# Pulsed_IR_LED.net
KiCad netlist of a schematic drawn in Altium Designer
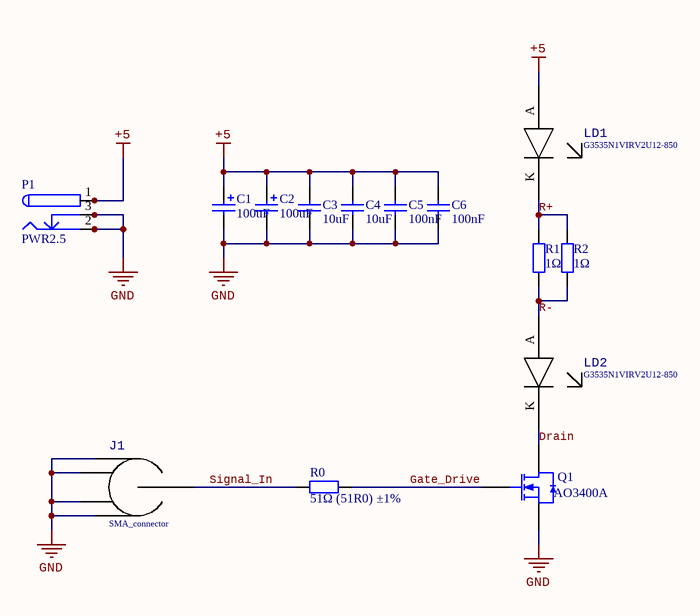
[diagram p0: Pulsed_IR_LED.SchDoc]

(export (version "E")
  (design (tool "Eeschema 10.0.6"))
  (components
    (comp (ref "C1")
      (value "100uF")
      (footprint "CASE-B_3528")
      (description "钽电容")
      (libsource (lib "JLC SMT Devices") (part "3528 100uF (107) 10% 6.3V"))
    )
    (comp (ref "C2")
      (value "100uF")
      (footprint "CASE-B_3528")
      (description "钽电容")
      (libsource (lib "JLC SMT Devices") (part "3528 100uF (107) 10% 6.3V"))
    )
    (comp (ref "C3")
      (value "10uF")
      (footprint "0805_C")
      (description "贴片电容")
      (libsource (lib "JLC SMT Devices") (part "0805 10uF (106) 10% 25V"))
    )
    (comp (ref "C4")
      (value "10uF")
      (footprint "0805_C")
      (description "贴片电容")
      (libsource (lib "JLC SMT Devices") (part "0805 10uF (106) 10% 25V"))
    )
    (comp (ref "C5")
      (value "100nF")
      (footprint "0603_C")
      (description "贴片电容")
      (libsource (lib "JLC SMT Devices") (part "0603 100nF (104) 10% 50V"))
    )
    (comp (ref "C6")
      (value "100nF")
      (footprint "0603_C")
      (description "贴片电容")
      (libsource (lib "JLC SMT Devices") (part "0603 100nF (104) 10% 50V"))
    )
    (comp (ref "J1")
      (value "SMA_connector")
      (footprint "SMA_header")
      (libsource (lib "SMA connector") (part "SMA_connector"))
    )
    (comp (ref "LD1")
      (value "G3535N1VIRV2U12-850")
      (footprint "3535VIR")
      (libsource (lib "IR_Vcsels") (part "G3535N1VIRV2U12-850"))
    )
    (comp (ref "LD2")
      (value "G3535N1VIRV2U12-850")
      (footprint "3535VIR")
      (libsource (lib "IR_Vcsels") (part "G3535N1VIRV2U12-850"))
    )
    (comp (ref "P1")
      (value "PWR2.5")
      (footprint "KLD-0202")
      (description "Low Voltage Power Supply Connector")
      (fields (field (name "PUBLISHER") "Altium Limited"))
      (libsource (lib "Miscellaneous Connectors") (part "PWR2.5"))
    )
    (comp (ref "Q1")
      (value "AO3400A")
      (footprint "SOT-23-3L")
      (description "MOS(场效应管)")
      (libsource (lib "JLC SMT Devices") (part "AO3400A N道沟 X0YV1T SOT-23"))
    )
    (comp (ref "R0")
      (value "51Ω (51R0) ±1%")
      (footprint "0402_R")
      (description "贴片电阻")
      (libsource (lib "JLC SMT Devices") (part "0402 51Ω (51R0) 1%"))
    )
    (comp (ref "R1")
      (value "1Ω")
      (footprint "1206_R")
      (description "贴片电阻")
      (libsource (lib "JLC SMT Devices") (part "1206 1Ω (1R00) 1%"))
    )
    (comp (ref "R2")
      (value "1Ω")
      (footprint "1206_R")
      (description "贴片电阻")
      (libsource (lib "JLC SMT Devices") (part "1206 1Ω (1R00) 1%"))
    )
  )
  (nets
    (net (code "1") (name "+5") (class "Default")
      (node (ref "C1") (pin "1") (pinfunction "1_1") (pintype "passive"))
      (node (ref "C2") (pin "1") (pinfunction "1_1") (pintype "passive"))
      (node (ref "C3") (pin "1") (pinfunction "1_1") (pintype "passive"))
      (node (ref "C4") (pin "1") (pinfunction "1_1") (pintype "passive"))
      (node (ref "C5") (pin "1") (pinfunction "1_1") (pintype "passive"))
      (node (ref "C6") (pin "1") (pinfunction "1_1") (pintype "passive"))
      (node (ref "LD1") (pin "A") (pinfunction "Anode_A") (pintype "passive"))
      (node (ref "P1") (pin "1") (pinfunction "1_1") (pintype "power_in"))
      (node (ref "P1") (pin "1A") (pinfunction "1A_1A") (pintype "power_in"))
      (node (ref "P1") (pin "1B") (pinfunction "1B_1B") (pintype "power_in"))
    )
    (net (code "2") (name "/Drain") (class "Default")
      (node (ref "LD2") (pin "K") (pinfunction "Cathode_K") (pintype "passive"))
      (node (ref "Q1") (pin "3") (pinfunction "D_3") (pintype "passive"))
    )
    (net (code "3") (name "/Gate_Drive") (class "Default")
      (node (ref "Q1") (pin "1") (pinfunction "G_1") (pintype "passive"))
      (node (ref "R0") (pin "2") (pinfunction "2_2") (pintype "passive"))
    )
    (net (code "4") (name "/R+") (class "Default")
      (node (ref "LD1") (pin "K") (pinfunction "Cathode_K") (pintype "passive"))
      (node (ref "R1") (pin "1") (pinfunction "1_1") (pintype "passive"))
      (node (ref "R2") (pin "1") (pinfunction "1_1") (pintype "passive"))
    )
    (net (code "5") (name "/R-") (class "Default")
      (node (ref "LD2") (pin "A") (pinfunction "Anode_A") (pintype "passive"))
      (node (ref "R1") (pin "2") (pinfunction "2_2") (pintype "passive"))
      (node (ref "R2") (pin "2") (pinfunction "2_2") (pintype "passive"))
    )
    (net (code "6") (name "/Signal_In") (class "Default")
      (node (ref "J1") (pin "1") (pinfunction "CORE_1") (pintype "passive"))
      (node (ref "R0") (pin "1") (pinfunction "1_1") (pintype "passive"))
    )
    (net (code "7") (name "GND") (class "Default")
      (node (ref "C1") (pin "2") (pinfunction "2_2") (pintype "passive"))
      (node (ref "C2") (pin "2") (pinfunction "2_2") (pintype "passive"))
      (node (ref "C3") (pin "2") (pinfunction "2_2") (pintype "passive"))
      (node (ref "C4") (pin "2") (pinfunction "2_2") (pintype "passive"))
      (node (ref "C5") (pin "2") (pinfunction "2_2") (pintype "passive"))
      (node (ref "C6") (pin "2") (pinfunction "2_2") (pintype "passive"))
      (node (ref "J1") (pin "2") (pinfunction "GND_2") (pintype "passive"))
      (node (ref "J1") (pin "3") (pinfunction "GND_3") (pintype "passive"))
      (node (ref "J1") (pin "4") (pinfunction "GND_4") (pintype "passive"))
      (node (ref "J1") (pin "5") (pinfunction "GND_5") (pintype "passive"))
      (node (ref "P1") (pin "2") (pinfunction "2_2") (pintype "power_in"))
      (node (ref "P1") (pin "2A") (pinfunction "2A_2A") (pintype "power_in"))
      (node (ref "P1") (pin "2B") (pinfunction "2B_2B") (pintype "power_in"))
      (node (ref "P1") (pin "3") (pinfunction "3_3") (pintype "power_in"))
      (node (ref "P1") (pin "3A") (pinfunction "3A_3A") (pintype "power_in"))
      (node (ref "P1") (pin "3B") (pinfunction "3B_3B") (pintype "power_in"))
      (node (ref "Q1") (pin "2") (pinfunction "S_2") (pintype "passive"))
    )
  )
)
